# hw-proto03.net
KiCad netlist of a schematic drawn in EAGLE
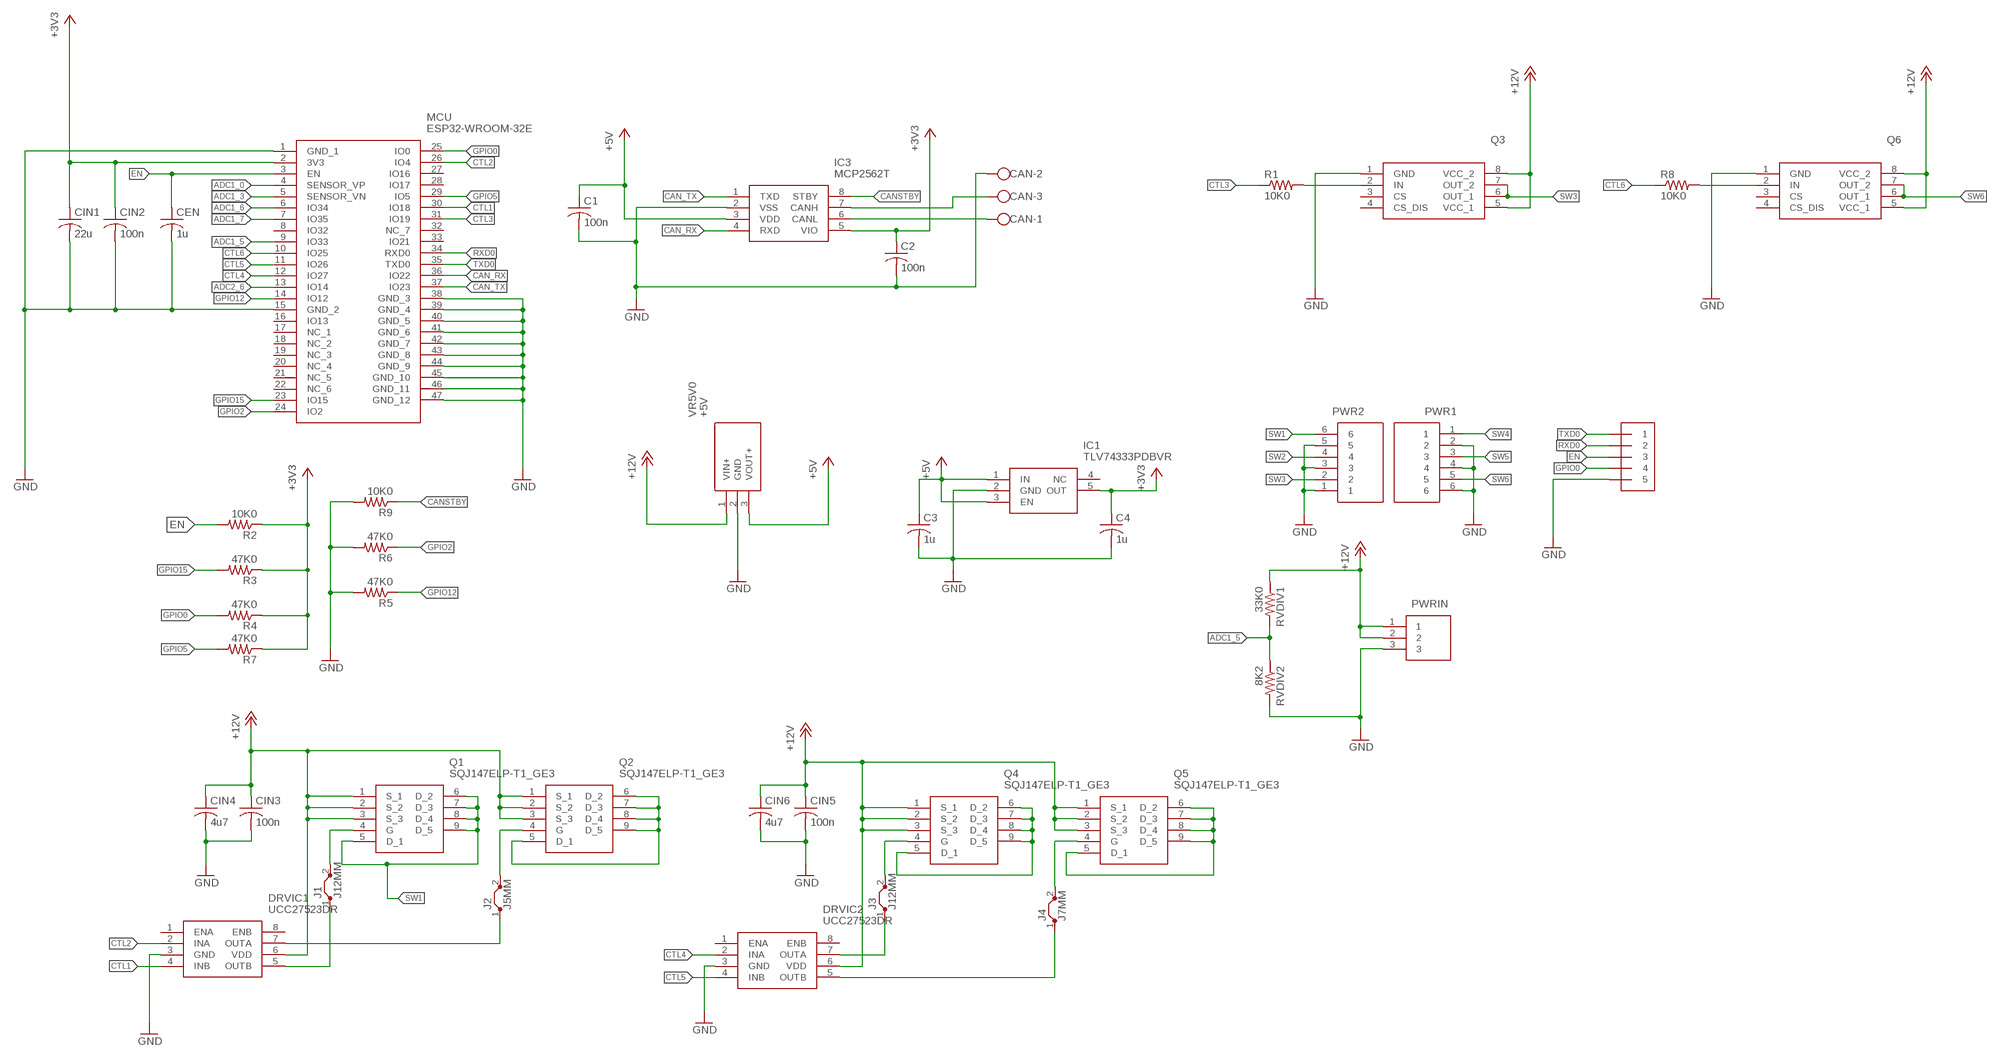
[diagram p0: schematic, sheet 1]

(export (version "E")
  (design (tool "Eeschema 10.0.6"))
  (components
    (comp (ref "C1")
      (value "100n")
      (footprint "eagle-import:C0603K")
      (libsource (lib "eagle-import") (part "C-USC0603K"))
    )
    (comp (ref "C2")
      (value "100n")
      (footprint "eagle-import:C0603K")
      (libsource (lib "eagle-import") (part "C-USC0603K"))
    )
    (comp (ref "C3")
      (value "1u")
      (footprint "eagle-import:C0603K")
      (libsource (lib "eagle-import") (part "C-USC0603K"))
    )
    (comp (ref "C4")
      (value "1u")
      (footprint "eagle-import:C0603K")
      (libsource (lib "eagle-import") (part "C-USC0603K"))
    )
    (comp (ref "CAN")
      (value "W237-103")
      (footprint "eagle-import:W237-103")
      (fields (field (name "MPN") "237-103"))
      (libsource (lib "eagle-import") (part "W237-103"))
    )
    (comp (ref "CEN")
      (value "1u")
      (footprint "eagle-import:C0603K")
      (libsource (lib "eagle-import") (part "C-USC0603K"))
    )
    (comp (ref "CIN1")
      (value "22u")
      (footprint "eagle-import:C0805K")
      (libsource (lib "eagle-import") (part "C-USC0805K"))
    )
    (comp (ref "CIN2")
      (value "100n")
      (footprint "eagle-import:C0603K")
      (libsource (lib "eagle-import") (part "C-USC0603K"))
    )
    (comp (ref "CIN3")
      (value "100n")
      (footprint "eagle-import:C0603K")
      (libsource (lib "eagle-import") (part "C-USC0603K"))
    )
    (comp (ref "CIN4")
      (value "4u7")
      (footprint "eagle-import:C0805K")
      (libsource (lib "eagle-import") (part "C-USC0805K"))
    )
    (comp (ref "CIN5")
      (value "100n")
      (footprint "eagle-import:C0603K")
      (libsource (lib "eagle-import") (part "C-USC0603K"))
    )
    (comp (ref "CIN6")
      (value "4u7")
      (footprint "eagle-import:C0805K")
      (libsource (lib "eagle-import") (part "C-USC0805K"))
    )
    (comp (ref "DRVIC1")
      (value "UCC27523DR")
      (footprint "eagle-import:SOIC127P600X175-8N")
      (fields (field (name "MOUSER_PART_NUMBER") "595-UCC27523DR"))
      (libsource (lib "eagle-import") (part "UCC27523DR"))
    )
    (comp (ref "DRVIC2")
      (value "UCC27523DR")
      (footprint "eagle-import:SOIC127P600X175-8N")
      (fields (field (name "MOUSER_PART_NUMBER") "595-UCC27523DR"))
      (libsource (lib "eagle-import") (part "UCC27523DR"))
    )
    (comp (ref "IC1")
      (value "TLV74333PDBVR")
      (footprint "eagle-import:SOT95P280X145-5N")
      (fields (field (name "MOUSER_PART_NUMBER") "595-TLV74333PDBVR"))
      (libsource (lib "eagle-import") (part "TLV74333PDBVR"))
    )
    (comp (ref "IC3")
      (value "MCP2562T")
      (footprint "eagle-import:SOIC127P600X175-8N")
      (fields
        (field (name "MANUFACTURER_PART_NUMBER") "MCP2562T-H/SN")
        (field (name "MOUSER_PART_NUMBER") "579-MCP2562T-H/SN")
      )
      (libsource (lib "eagle-import") (part "MCP2562T-H_SN"))
    )
    (comp (ref "J1")
      (value "J12MM")
      (footprint "eagle-import:12")
      (libsource (lib "eagle-import") (part "J12MM"))
    )
    (comp (ref "J2")
      (value "J5MM")
      (footprint "eagle-import:05")
      (libsource (lib "eagle-import") (part "J5MM"))
    )
    (comp (ref "J3")
      (value "J12MM")
      (footprint "eagle-import:12")
      (libsource (lib "eagle-import") (part "J12MM"))
    )
    (comp (ref "J4")
      (value "J7MM")
      (footprint "eagle-import:07")
      (libsource (lib "eagle-import") (part "J7MM"))
    )
    (comp (ref "MCU")
      (value "ESP32-WROOM-32E")
      (footprint "eagle-import:ESP32WROOM32EN8R2")
      (fields
        (field (name "MANUFACTURER_PART_NUMBER") "ESP32-WROOM-32E-N8R2")
        (field (name "MOUSER_PART_NUMBER") "356-ESP32WRM32EN8R2")
      )
      (libsource (lib "eagle-import") (part "ESP32-WROOM-32E-N8R2"))
    )
    (comp (ref "PROG")
      (value "1X5")
      (footprint "eagle-import:1X05-3.5MM")
      (libsource (lib "eagle-import") (part "1X5"))
    )
    (comp (ref "PWR1")
      (value "4DB-P108-06")
      (footprint "eagle-import:4DBP10806")
      (libsource (lib "eagle-import") (part "4DB-P108-06"))
    )
    (comp (ref "PWR2")
      (value "4DB-P108-06")
      (footprint "eagle-import:4DBP10806")
      (libsource (lib "eagle-import") (part "4DB-P108-06"))
    )
    (comp (ref "PWRIN")
      (value "4DB-P108-03")
      (footprint "eagle-import:4DBP10803")
      (fields (field (name "MOUSER_PART_NUMBER") "571-214376675"))
      (libsource (lib "eagle-import") (part "4DB-P108-03"))
    )
    (comp (ref "Q1")
      (value "SQJ147ELP-T1_GE3")
      (footprint "eagle-import:SQJ147ELPT1_GE3")
      (fields (field (name "MOUSER_PART_NUMBER") "78-SQJ147ELP-T1_GE3"))
      (libsource (lib "eagle-import") (part "SQJ147ELP-T1_GE3"))
    )
    (comp (ref "Q2")
      (value "SQJ147ELP-T1_GE3")
      (footprint "eagle-import:SQJ147ELPT1_GE3")
      (fields (field (name "MOUSER_PART_NUMBER") "78-SQJ147ELP-T1_GE3"))
      (libsource (lib "eagle-import") (part "SQJ147ELP-T1_GE3"))
    )
    (comp (ref "Q3")
      (value "VN5E160MSTR-E")
      (footprint "eagle-import:SOIC127P600X175-8N")
      (fields (field (name "MOUSER_PART_NUMBER") "511-VN5E160MSTR-E"))
      (libsource (lib "eagle-import") (part "VN5E160MSTR-E"))
    )
    (comp (ref "Q4")
      (value "SQJ147ELP-T1_GE3")
      (footprint "eagle-import:SQJ147ELPT1_GE3")
      (fields (field (name "MOUSER_PART_NUMBER") "78-SQJ147ELP-T1_GE3"))
      (libsource (lib "eagle-import") (part "SQJ147ELP-T1_GE3"))
    )
    (comp (ref "Q5")
      (value "SQJ147ELP-T1_GE3")
      (footprint "eagle-import:SQJ147ELPT1_GE3")
      (fields (field (name "MOUSER_PART_NUMBER") "78-SQJ147ELP-T1_GE3"))
      (libsource (lib "eagle-import") (part "SQJ147ELP-T1_GE3"))
    )
    (comp (ref "Q6")
      (value "VN5E160MSTR-E")
      (footprint "eagle-import:SOIC127P600X175-8N")
      (fields (field (name "MOUSER_PART_NUMBER") "511-VN5E160MSTR-E"))
      (libsource (lib "eagle-import") (part "VN5E160MSTR-E"))
    )
    (comp (ref "R1")
      (value "10K0")
      (footprint "eagle-import:0204_7")
      (libsource (lib "eagle-import") (part "R-US_0204/7"))
    )
    (comp (ref "R2")
      (value "10K0")
      (footprint "eagle-import:R0603")
      (libsource (lib "eagle-import") (part "R-US_R0603"))
    )
    (comp (ref "R3")
      (value "47K0")
      (footprint "eagle-import:R0603")
      (libsource (lib "eagle-import") (part "R-US_R0603"))
    )
    (comp (ref "R4")
      (value "47K0")
      (footprint "eagle-import:R0603")
      (libsource (lib "eagle-import") (part "R-US_R0603"))
    )
    (comp (ref "R5")
      (value "47K0")
      (footprint "eagle-import:R0603")
      (libsource (lib "eagle-import") (part "R-US_R0603"))
    )
    (comp (ref "R6")
      (value "47K0")
      (footprint "eagle-import:R0603")
      (libsource (lib "eagle-import") (part "R-US_R0603"))
    )
    (comp (ref "R7")
      (value "47K0")
      (footprint "eagle-import:R0603")
      (libsource (lib "eagle-import") (part "R-US_R0603"))
    )
    (comp (ref "R8")
      (value "10K0")
      (footprint "eagle-import:0207_12")
      (libsource (lib "eagle-import") (part "R-US_0207/12"))
    )
    (comp (ref "R9")
      (value "10K0")
      (footprint "eagle-import:R0603")
      (libsource (lib "eagle-import") (part "R-US_R0603"))
    )
    (comp (ref "RVDIV1")
      (value "33K0")
      (footprint "eagle-import:R0603")
      (libsource (lib "eagle-import") (part "R-US_R0603"))
    )
    (comp (ref "RVDIV2")
      (value "8K2")
      (footprint "eagle-import:R0603")
      (libsource (lib "eagle-import") (part "R-US_R0603"))
    )
    (comp (ref "VR5V0")
      (value "+5V")
      (footprint "eagle-import:TSR-1-2433")
      (fields
        (field (name "MANUFACTURER_PART_NUMBER") "TSR 1-2433E")
        (field (name "MOUSER_PART_NUMBER") "495-TSR1-2433E")
      )
      (libsource (lib "eagle-import") (part "TSR_1-2433E"))
    )
  )
  (nets
    (net (code "1") (name "+3V3") (class "Default")
      (node (ref "C2") (pin "1") (pinfunction "1_1") (pintype "passive"))
      (node (ref "C4") (pin "1") (pinfunction "1_1") (pintype "passive"))
      (node (ref "CIN1") (pin "1") (pinfunction "1_1") (pintype "passive"))
      (node (ref "CIN2") (pin "1") (pinfunction "1_1") (pintype "passive"))
      (node (ref "IC1") (pin "5") (pinfunction "OUT_5") (pintype "bidirectional"))
      (node (ref "IC3") (pin "5") (pinfunction "VIO_5") (pintype "bidirectional"))
      (node (ref "MCU") (pin "2") (pinfunction "3V3_2") (pintype "bidirectional"))
      (node (ref "R2") (pin "1") (pinfunction "1_1") (pintype "passive"))
      (node (ref "R3") (pin "1") (pinfunction "1_1") (pintype "passive"))
      (node (ref "R4") (pin "1") (pinfunction "1_1") (pintype "passive"))
      (node (ref "R7") (pin "1") (pinfunction "1_1") (pintype "passive"))
    )
    (net (code "2") (name "+5V") (class "Default")
      (node (ref "C1") (pin "1") (pinfunction "1_1") (pintype "passive"))
      (node (ref "C3") (pin "1") (pinfunction "1_1") (pintype "passive"))
      (node (ref "IC1") (pin "1") (pinfunction "IN_1") (pintype "bidirectional"))
      (node (ref "IC1") (pin "3") (pinfunction "EN_3") (pintype "bidirectional"))
      (node (ref "IC3") (pin "3") (pinfunction "VDD_3") (pintype "bidirectional"))
      (node (ref "VR5V0") (pin "3") (pinfunction "VOUT+_3") (pintype "output"))
    )
    (net (code "3") (name "+12V") (class "Default")
      (node (ref "CIN3") (pin "1") (pinfunction "1_1") (pintype "passive"))
      (node (ref "CIN4") (pin "1") (pinfunction "1_1") (pintype "passive"))
      (node (ref "CIN5") (pin "1") (pinfunction "1_1") (pintype "passive"))
      (node (ref "CIN6") (pin "1") (pinfunction "1_1") (pintype "passive"))
      (node (ref "DRVIC1") (pin "6") (pinfunction "VDD_6") (pintype "bidirectional"))
      (node (ref "DRVIC2") (pin "6") (pinfunction "VDD_6") (pintype "bidirectional"))
      (node (ref "PWRIN") (pin "1") (pinfunction "1_1") (pintype "bidirectional"))
      (node (ref "PWRIN") (pin "2") (pinfunction "2_2") (pintype "bidirectional"))
      (node (ref "Q1") (pin "1") (pinfunction "S_1_1") (pintype "bidirectional"))
      (node (ref "Q1") (pin "2") (pinfunction "S_2_2") (pintype "bidirectional"))
      (node (ref "Q1") (pin "3") (pinfunction "S_3_3") (pintype "bidirectional"))
      (node (ref "Q2") (pin "1") (pinfunction "S_1_1") (pintype "bidirectional"))
      (node (ref "Q2") (pin "2") (pinfunction "S_2_2") (pintype "bidirectional"))
      (node (ref "Q2") (pin "3") (pinfunction "S_3_3") (pintype "bidirectional"))
      (node (ref "Q3") (pin "5") (pinfunction "VCC_1_5") (pintype "bidirectional"))
      (node (ref "Q3") (pin "8") (pinfunction "VCC_2_8") (pintype "bidirectional"))
      (node (ref "Q4") (pin "1") (pinfunction "S_1_1") (pintype "bidirectional"))
      (node (ref "Q4") (pin "2") (pinfunction "S_2_2") (pintype "bidirectional"))
      (node (ref "Q4") (pin "3") (pinfunction "S_3_3") (pintype "bidirectional"))
      (node (ref "Q5") (pin "1") (pinfunction "S_1_1") (pintype "bidirectional"))
      (node (ref "Q5") (pin "2") (pinfunction "S_2_2") (pintype "bidirectional"))
      (node (ref "Q5") (pin "3") (pinfunction "S_3_3") (pintype "bidirectional"))
      (node (ref "Q6") (pin "5") (pinfunction "VCC_1_5") (pintype "bidirectional"))
      (node (ref "Q6") (pin "8") (pinfunction "VCC_2_8") (pintype "bidirectional"))
      (node (ref "RVDIV1") (pin "1") (pinfunction "1_1") (pintype "passive"))
      (node (ref "VR5V0") (pin "1") (pinfunction "VIN+_1") (pintype "input"))
    )
    (net (code "4") (name "ADC1_0") (class "Default")
      (node (ref "MCU") (pin "4") (pinfunction "SENSOR_VP_4") (pintype "bidirectional"))
    )
    (net (code "5") (name "ADC1_3") (class "Default")
      (node (ref "MCU") (pin "5") (pinfunction "SENSOR_VN_5") (pintype "bidirectional"))
    )
    (net (code "6") (name "ADC1_5") (class "Default")
      (node (ref "MCU") (pin "9") (pinfunction "IO33_9") (pintype "bidirectional"))
      (node (ref "RVDIV1") (pin "2") (pinfunction "2_2") (pintype "passive"))
      (node (ref "RVDIV2") (pin "1") (pinfunction "1_1") (pintype "passive"))
    )
    (net (code "7") (name "ADC1_6") (class "Default")
      (node (ref "MCU") (pin "6") (pinfunction "IO34_6") (pintype "bidirectional"))
    )
    (net (code "8") (name "ADC1_7") (class "Default")
      (node (ref "MCU") (pin "7") (pinfunction "IO35_7") (pintype "bidirectional"))
    )
    (net (code "9") (name "ADC2_6") (class "Default")
      (node (ref "MCU") (pin "13") (pinfunction "IO14_13") (pintype "bidirectional"))
    )
    (net (code "10") (name "CANSTBY") (class "Default")
      (node (ref "IC3") (pin "8") (pinfunction "STBY_8") (pintype "bidirectional"))
      (node (ref "R9") (pin "1") (pinfunction "1_1") (pintype "passive"))
    )
    (net (code "11") (name "CAN_RX") (class "Default")
      (node (ref "IC3") (pin "4") (pinfunction "RXD_4") (pintype "bidirectional"))
      (node (ref "MCU") (pin "36") (pinfunction "IO22_36") (pintype "bidirectional"))
    )
    (net (code "12") (name "CAN_TX") (class "Default")
      (node (ref "IC3") (pin "1") (pinfunction "TXD_1") (pintype "bidirectional"))
      (node (ref "MCU") (pin "37") (pinfunction "IO23_37") (pintype "bidirectional"))
    )
    (net (code "13") (name "CTL1") (class "Default")
      (node (ref "DRVIC1") (pin "4") (pinfunction "INB_4") (pintype "bidirectional"))
      (node (ref "MCU") (pin "30") (pinfunction "IO18_30") (pintype "bidirectional"))
    )
    (net (code "14") (name "CTL2") (class "Default")
      (node (ref "DRVIC1") (pin "2") (pinfunction "INA_2") (pintype "bidirectional"))
      (node (ref "MCU") (pin "26") (pinfunction "IO4_26") (pintype "bidirectional"))
    )
    (net (code "15") (name "CTL3") (class "Default")
      (node (ref "MCU") (pin "31") (pinfunction "IO19_31") (pintype "bidirectional"))
      (node (ref "R1") (pin "1") (pinfunction "1_1") (pintype "passive"))
    )
    (net (code "16") (name "CTL4") (class "Default")
      (node (ref "DRVIC2") (pin "2") (pinfunction "INA_2") (pintype "bidirectional"))
      (node (ref "MCU") (pin "12") (pinfunction "IO27_12") (pintype "bidirectional"))
    )
    (net (code "17") (name "CTL5") (class "Default")
      (node (ref "DRVIC2") (pin "4") (pinfunction "INB_4") (pintype "bidirectional"))
      (node (ref "MCU") (pin "11") (pinfunction "IO26_11") (pintype "bidirectional"))
    )
    (net (code "18") (name "CTL6") (class "Default")
      (node (ref "MCU") (pin "10") (pinfunction "IO25_10") (pintype "bidirectional"))
      (node (ref "R8") (pin "1") (pinfunction "1_1") (pintype "passive"))
    )
    (net (code "19") (name "EN") (class "Default")
      (node (ref "CEN") (pin "1") (pinfunction "1_1") (pintype "passive"))
      (node (ref "MCU") (pin "3") (pinfunction "EN_3") (pintype "bidirectional"))
      (node (ref "PROG") (pin "3") (pinfunction "3_3") (pintype "passive"))
      (node (ref "R2") (pin "2") (pinfunction "2_2") (pintype "passive"))
    )
    (net (code "20") (name "GND") (class "Default")
      (node (ref "C1") (pin "2") (pinfunction "2_2") (pintype "passive"))
      (node (ref "C2") (pin "2") (pinfunction "2_2") (pintype "passive"))
      (node (ref "C3") (pin "2") (pinfunction "2_2") (pintype "passive"))
      (node (ref "C4") (pin "2") (pinfunction "2_2") (pintype "passive"))
      (node (ref "CAN") (pin "2") (pinfunction "KL_2") (pintype "passive"))
      (node (ref "CEN") (pin "2") (pinfunction "2_2") (pintype "passive"))
      (node (ref "CIN1") (pin "2") (pinfunction "2_2") (pintype "passive"))
      (node (ref "CIN2") (pin "2") (pinfunction "2_2") (pintype "passive"))
      (node (ref "CIN3") (pin "2") (pinfunction "2_2") (pintype "passive"))
      (node (ref "CIN4") (pin "2") (pinfunction "2_2") (pintype "passive"))
      (node (ref "CIN5") (pin "2") (pinfunction "2_2") (pintype "passive"))
      (node (ref "CIN6") (pin "2") (pinfunction "2_2") (pintype "passive"))
      (node (ref "DRVIC1") (pin "3") (pinfunction "GND_3") (pintype "bidirectional"))
      (node (ref "DRVIC2") (pin "3") (pinfunction "GND_3") (pintype "bidirectional"))
      (node (ref "IC1") (pin "2") (pinfunction "GND_2") (pintype "bidirectional"))
      (node (ref "IC3") (pin "2") (pinfunction "VSS_2") (pintype "bidirectional"))
      (node (ref "MCU") (pin "1") (pinfunction "GND_1_1") (pintype "bidirectional"))
      (node (ref "MCU") (pin "15") (pinfunction "GND_2_15") (pintype "bidirectional"))
      (node (ref "MCU") (pin "38") (pinfunction "GND_3_38") (pintype "bidirectional"))
      (node (ref "MCU") (pin "39") (pinfunction "GND_4_39") (pintype "bidirectional"))
      (node (ref "MCU") (pin "40") (pinfunction "GND_5_40") (pintype "bidirectional"))
      (node (ref "MCU") (pin "41") (pinfunction "GND_6_41") (pintype "bidirectional"))
      (node (ref "MCU") (pin "42") (pinfunction "GND_7_42") (pintype "bidirectional"))
      (node (ref "MCU") (pin "43") (pinfunction "GND_8_43") (pintype "bidirectional"))
      (node (ref "MCU") (pin "44") (pinfunction "GND_9_44") (pintype "bidirectional"))
      (node (ref "MCU") (pin "45") (pinfunction "GND_10_45") (pintype "bidirectional"))
      (node (ref "MCU") (pin "46") (pinfunction "GND_11_46") (pintype "bidirectional"))
      (node (ref "MCU") (pin "47") (pinfunction "GND_12_47") (pintype "bidirectional"))
      (node (ref "PROG") (pin "5") (pinfunction "5_5") (pintype "passive"))
      (node (ref "PWR1") (pin "2") (pinfunction "2_2") (pintype "bidirectional"))
      (node (ref "PWR1") (pin "4") (pinfunction "4_4") (pintype "bidirectional"))
      (node (ref "PWR1") (pin "6") (pinfunction "6_6") (pintype "bidirectional"))
      (node (ref "PWR2") (pin "1") (pinfunction "1_1") (pintype "bidirectional"))
      (node (ref "PWR2") (pin "3") (pinfunction "3_3") (pintype "bidirectional"))
      (node (ref "PWR2") (pin "5") (pinfunction "5_5") (pintype "bidirectional"))
      (node (ref "PWRIN") (pin "3") (pinfunction "3_3") (pintype "bidirectional"))
      (node (ref "Q3") (pin "1") (pinfunction "GND_1") (pintype "bidirectional"))
      (node (ref "Q6") (pin "1") (pinfunction "GND_1") (pintype "bidirectional"))
      (node (ref "R5") (pin "2") (pinfunction "2_2") (pintype "passive"))
      (node (ref "R6") (pin "2") (pinfunction "2_2") (pintype "passive"))
      (node (ref "R9") (pin "2") (pinfunction "2_2") (pintype "passive"))
      (node (ref "RVDIV2") (pin "2") (pinfunction "2_2") (pintype "passive"))
      (node (ref "VR5V0") (pin "2") (pinfunction "GND_2") (pintype "power_in"))
    )
    (net (code "21") (name "GPIO0") (class "Default")
      (node (ref "MCU") (pin "25") (pinfunction "IO0_25") (pintype "bidirectional"))
      (node (ref "PROG") (pin "4") (pinfunction "4_4") (pintype "passive"))
      (node (ref "R4") (pin "2") (pinfunction "2_2") (pintype "passive"))
    )
    (net (code "22") (name "GPIO2") (class "Default")
      (node (ref "MCU") (pin "24") (pinfunction "IO2_24") (pintype "bidirectional"))
      (node (ref "R6") (pin "1") (pinfunction "1_1") (pintype "passive"))
    )
    (net (code "23") (name "GPIO5") (class "Default")
      (node (ref "MCU") (pin "29") (pinfunction "IO5_29") (pintype "bidirectional"))
      (node (ref "R7") (pin "2") (pinfunction "2_2") (pintype "passive"))
    )
    (net (code "24") (name "GPIO12") (class "Default")
      (node (ref "MCU") (pin "14") (pinfunction "IO12_14") (pintype "bidirectional"))
      (node (ref "R5") (pin "1") (pinfunction "1_1") (pintype "passive"))
    )
    (net (code "25") (name "GPIO15") (class "Default")
      (node (ref "MCU") (pin "23") (pinfunction "IO15_23") (pintype "bidirectional"))
      (node (ref "R3") (pin "2") (pinfunction "2_2") (pintype "passive"))
    )
    (net (code "26") (name "Net-(CANA-KL)") (class "Default")
      (node (ref "CAN") (pin "1") (pinfunction "KL_1") (pintype "passive"))
      (node (ref "IC3") (pin "6") (pinfunction "CANL_6") (pintype "bidirectional"))
    )
    (net (code "27") (name "Net-(CANC-KL)") (class "Default")
      (node (ref "CAN") (pin "3") (pinfunction "KL_3") (pintype "passive"))
      (node (ref "IC3") (pin "7") (pinfunction "CANH_7") (pintype "bidirectional"))
    )
    (net (code "28") (name "Net-(DRVIC1-OUTA)") (class "Default")
      (node (ref "DRVIC1") (pin "7") (pinfunction "OUTA_7") (pintype "bidirectional"))
      (node (ref "J2") (pin "1") (pinfunction "1_1") (pintype "passive"))
    )
    (net (code "29") (name "Net-(DRVIC1-OUTB)") (class "Default")
      (node (ref "DRVIC1") (pin "5") (pinfunction "OUTB_5") (pintype "bidirectional"))
      (node (ref "J1") (pin "1") (pinfunction "1_1") (pintype "passive"))
    )
    (net (code "30") (name "Net-(DRVIC2-OUTA)") (class "Default")
      (node (ref "DRVIC2") (pin "7") (pinfunction "OUTA_7") (pintype "bidirectional"))
      (node (ref "J3") (pin "1") (pinfunction "1_1") (pintype "passive"))
    )
    (net (code "31") (name "Net-(DRVIC2-OUTB)") (class "Default")
      (node (ref "DRVIC2") (pin "5") (pinfunction "OUTB_5") (pintype "bidirectional"))
      (node (ref "J4") (pin "1") (pinfunction "1_1") (pintype "passive"))
    )
    (net (code "32") (name "Net-(Q1-G)") (class "Default")
      (node (ref "J1") (pin "2") (pinfunction "2_2") (pintype "passive"))
      (node (ref "Q1") (pin "4") (pinfunction "G_4") (pintype "bidirectional"))
    )
    (net (code "33") (name "Net-(Q2-G)") (class "Default")
      (node (ref "J2") (pin "2") (pinfunction "2_2") (pintype "passive"))
      (node (ref "Q2") (pin "4") (pinfunction "G_4") (pintype "bidirectional"))
    )
    (net (code "34") (name "Net-(Q3-IN)") (class "Default")
      (node (ref "Q3") (pin "2") (pinfunction "IN_2") (pintype "bidirectional"))
      (node (ref "R1") (pin "2") (pinfunction "2_2") (pintype "passive"))
    )
    (net (code "35") (name "Net-(Q4-G)") (class "Default")
      (node (ref "J3") (pin "2") (pinfunction "2_2") (pintype "passive"))
      (node (ref "Q4") (pin "4") (pinfunction "G_4") (pintype "bidirectional"))
    )
    (net (code "36") (name "Net-(Q5-G)") (class "Default")
      (node (ref "J4") (pin "2") (pinfunction "2_2") (pintype "passive"))
      (node (ref "Q5") (pin "4") (pinfunction "G_4") (pintype "bidirectional"))
    )
    (net (code "37") (name "Net-(Q6-IN)") (class "Default")
      (node (ref "Q6") (pin "2") (pinfunction "IN_2") (pintype "bidirectional"))
      (node (ref "R8") (pin "2") (pinfunction "2_2") (pintype "passive"))
    )
    (net (code "38") (name "RXD0") (class "Default")
      (node (ref "MCU") (pin "34") (pinfunction "RXD0_34") (pintype "bidirectional"))
      (node (ref "PROG") (pin "2") (pinfunction "2_2") (pintype "passive"))
    )
    (net (code "39") (name "SW1") (class "Default")
      (node (ref "PWR2") (pin "6") (pinfunction "6_6") (pintype "bidirectional"))
      (node (ref "Q1") (pin "5") (pinfunction "D_1_5") (pintype "bidirectional"))
      (node (ref "Q1") (pin "6") (pinfunction "D_2_6") (pintype "bidirectional"))
      (node (ref "Q1") (pin "7") (pinfunction "D_3_7") (pintype "bidirectional"))
      (node (ref "Q1") (pin "8") (pinfunction "D_4_8") (pintype "bidirectional"))
      (node (ref "Q1") (pin "9") (pinfunction "D_5_9") (pintype "bidirectional"))
    )
    (net (code "40") (name "SW2") (class "Default")
      (node (ref "PWR2") (pin "4") (pinfunction "4_4") (pintype "bidirectional"))
      (node (ref "Q2") (pin "5") (pinfunction "D_1_5") (pintype "bidirectional"))
      (node (ref "Q2") (pin "6") (pinfunction "D_2_6") (pintype "bidirectional"))
      (node (ref "Q2") (pin "7") (pinfunction "D_3_7") (pintype "bidirectional"))
      (node (ref "Q2") (pin "8") (pinfunction "D_4_8") (pintype "bidirectional"))
      (node (ref "Q2") (pin "9") (pinfunction "D_5_9") (pintype "bidirectional"))
    )
    (net (code "41") (name "SW3") (class "Default")
      (node (ref "PWR2") (pin "2") (pinfunction "2_2") (pintype "bidirectional"))
      (node (ref "Q3") (pin "6") (pinfunction "OUT_1_6") (pintype "bidirectional"))
      (node (ref "Q3") (pin "7") (pinfunction "OUT_2_7") (pintype "bidirectional"))
    )
    (net (code "42") (name "SW4") (class "Default")
      (node (ref "PWR1") (pin "1") (pinfunction "1_1") (pintype "bidirectional"))
      (node (ref "Q4") (pin "5") (pinfunction "D_1_5") (pintype "bidirectional"))
      (node (ref "Q4") (pin "6") (pinfunction "D_2_6") (pintype "bidirectional"))
      (node (ref "Q4") (pin "7") (pinfunction "D_3_7") (pintype "bidirectional"))
      (node (ref "Q4") (pin "8") (pinfunction "D_4_8") (pintype "bidirectional"))
      (node (ref "Q4") (pin "9") (pinfunction "D_5_9") (pintype "bidirectional"))
    )
    (net (code "43") (name "SW5") (class "Default")
      (node (ref "PWR1") (pin "3") (pinfunction "3_3") (pintype "bidirectional"))
      (node (ref "Q5") (pin "5") (pinfunction "D_1_5") (pintype "bidirectional"))
      (node (ref "Q5") (pin "6") (pinfunction "D_2_6") (pintype "bidirectional"))
      (node (ref "Q5") (pin "7") (pinfunction "D_3_7") (pintype "bidirectional"))
      (node (ref "Q5") (pin "8") (pinfunction "D_4_8") (pintype "bidirectional"))
      (node (ref "Q5") (pin "9") (pinfunction "D_5_9") (pintype "bidirectional"))
    )
    (net (code "44") (name "SW6") (class "Default")
      (node (ref "PWR1") (pin "5") (pinfunction "5_5") (pintype "bidirectional"))
      (node (ref "Q6") (pin "6") (pinfunction "OUT_1_6") (pintype "bidirectional"))
      (node (ref "Q6") (pin "7") (pinfunction "OUT_2_7") (pintype "bidirectional"))
    )
    (net (code "45") (name "TXD0") (class "Default")
      (node (ref "MCU") (pin "35") (pinfunction "TXD0_35") (pintype "bidirectional"))
      (node (ref "PROG") (pin "1") (pinfunction "1_1") (pintype "passive"))
    )
    (net (code "46") (name "unconnected-(DRVIC1-ENA-Pad1)") (class "Default")
      (node (ref "DRVIC1") (pin "1") (pinfunction "ENA_1") (pintype "bidirectional"))
    )
    (net (code "47") (name "unconnected-(DRVIC1-ENB-Pad8)") (class "Default")
      (node (ref "DRVIC1") (pin "8") (pinfunction "ENB_8") (pintype "bidirectional"))
    )
    (net (code "48") (name "unconnected-(DRVIC2-ENA-Pad1)") (class "Default")
      (node (ref "DRVIC2") (pin "1") (pinfunction "ENA_1") (pintype "bidirectional"))
    )
    (net (code "49") (name "unconnected-(DRVIC2-ENB-Pad8)") (class "Default")
      (node (ref "DRVIC2") (pin "8") (pinfunction "ENB_8") (pintype "bidirectional"))
    )
    (net (code "50") (name "unconnected-(IC1-NC-Pad4)") (class "Default")
      (node (ref "IC1") (pin "4") (pinfunction "NC_4") (pintype "no_connect"))
    )
    (net (code "51") (name "unconnected-(MCU-IO13-Pad16)") (class "Default")
      (node (ref "MCU") (pin "16") (pinfunction "IO13_16") (pintype "bidirectional"))
    )
    (net (code "52") (name "unconnected-(MCU-IO16-Pad27)") (class "Default")
      (node (ref "MCU") (pin "27") (pinfunction "IO16_27") (pintype "bidirectional"))
    )
    (net (code "53") (name "unconnected-(MCU-IO17-Pad28)") (class "Default")
      (node (ref "MCU") (pin "28") (pinfunction "IO17_28") (pintype "bidirectional"))
    )
    (net (code "54") (name "unconnected-(MCU-IO21-Pad33)") (class "Default")
      (node (ref "MCU") (pin "33") (pinfunction "IO21_33") (pintype "bidirectional"))
    )
    (net (code "55") (name "unconnected-(MCU-IO32-Pad8)") (class "Default")
      (node (ref "MCU") (pin "8") (pinfunction "IO32_8") (pintype "bidirectional"))
    )
    (net (code "56") (name "unconnected-(MCU-NC_1-Pad17)") (class "Default")
      (node (ref "MCU") (pin "17") (pinfunction "NC_1_17") (pintype "bidirectional"))
    )
    (net (code "57") (name "unconnected-(MCU-NC_2-Pad18)") (class "Default")
      (node (ref "MCU") (pin "18") (pinfunction "NC_2_18") (pintype "bidirectional"))
    )
    (net (code "58") (name "unconnected-(MCU-NC_3-Pad19)") (class "Default")
      (node (ref "MCU") (pin "19") (pinfunction "NC_3_19") (pintype "bidirectional"))
    )
    (net (code "59") (name "unconnected-(MCU-NC_4-Pad20)") (class "Default")
      (node (ref "MCU") (pin "20") (pinfunction "NC_4_20") (pintype "bidirectional"))
    )
    (net (code "60") (name "unconnected-(MCU-NC_5-Pad21)") (class "Default")
      (node (ref "MCU") (pin "21") (pinfunction "NC_5_21") (pintype "bidirectional"))
    )
    (net (code "61") (name "unconnected-(MCU-NC_6-Pad22)") (class "Default")
      (node (ref "MCU") (pin "22") (pinfunction "NC_6_22") (pintype "bidirectional"))
    )
    (net (code "62") (name "unconnected-(MCU-NC_7-Pad32)") (class "Default")
      (node (ref "MCU") (pin "32") (pinfunction "NC_7_32") (pintype "bidirectional"))
    )
    (net (code "63") (name "unconnected-(Q3-CS-Pad3)") (class "Default")
      (node (ref "Q3") (pin "3") (pinfunction "CS_3") (pintype "bidirectional"))
    )
    (net (code "64") (name "unconnected-(Q3-CS_DIS-Pad4)") (class "Default")
      (node (ref "Q3") (pin "4") (pinfunction "CS_DIS_4") (pintype "bidirectional"))
    )
    (net (code "65") (name "unconnected-(Q6-CS-Pad3)") (class "Default")
      (node (ref "Q6") (pin "3") (pinfunction "CS_3") (pintype "bidirectional"))
    )
    (net (code "66") (name "unconnected-(Q6-CS_DIS-Pad4)") (class "Default")
      (node (ref "Q6") (pin "4") (pinfunction "CS_DIS_4") (pintype "bidirectional"))
    )
  )
)
